# rf_bpf.net
KiCad netlist of a schematic drawn in Altium Designer
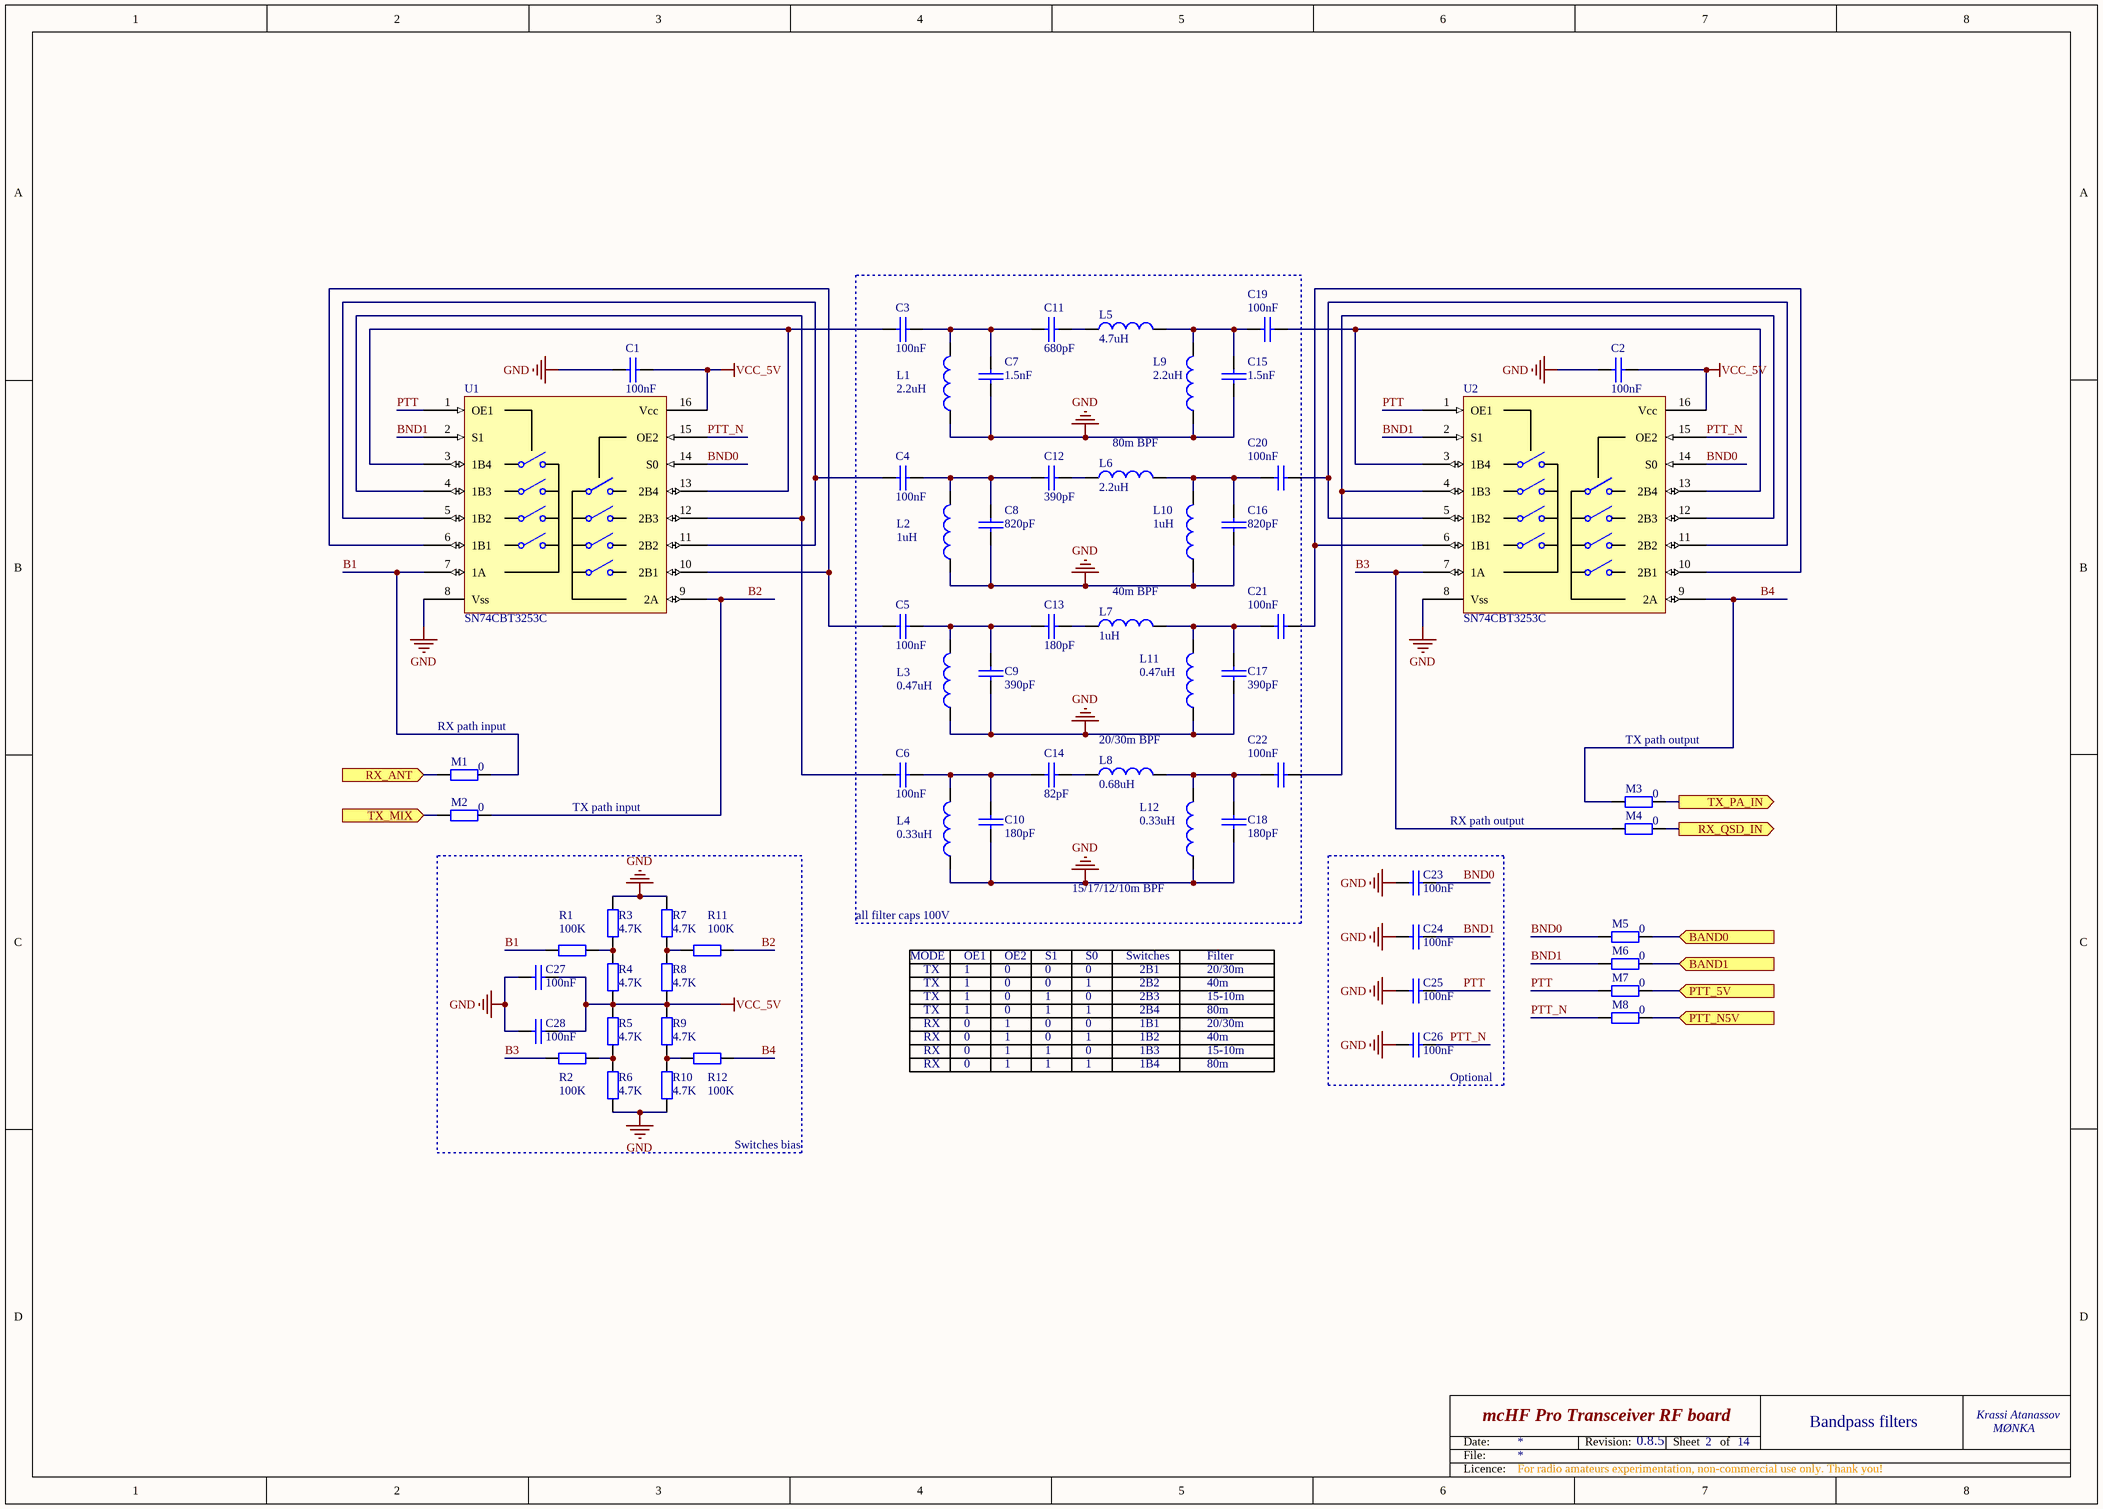
[diagram p0: rf_bpf.SchDoc]

(export (version "E")
  (design (tool "Eeschema 10.0.6"))
  (components
    (comp (ref "C1")
      (value "100nF")
      (footprint "0805")
      (description "Capacitor")
      (libsource (lib "mcHF_rf") (part "CAP"))
    )
    (comp (ref "C2")
      (value "100nF")
      (footprint "0805")
      (description "Capacitor")
      (libsource (lib "mcHF_rf") (part "CAP"))
    )
    (comp (ref "C3")
      (value "100nF")
      (footprint "0805")
      (description "Capacitor")
      (libsource (lib "mcHF_rf") (part "CAP"))
    )
    (comp (ref "C4")
      (value "100nF")
      (footprint "0805")
      (description "Capacitor")
      (libsource (lib "mcHF_rf") (part "CAP"))
    )
    (comp (ref "C5")
      (value "100nF")
      (footprint "0805")
      (description "Capacitor")
      (libsource (lib "mcHF_rf") (part "CAP"))
    )
    (comp (ref "C6")
      (value "100nF")
      (footprint "0805")
      (description "Capacitor")
      (libsource (lib "mcHF_rf") (part "CAP"))
    )
    (comp (ref "C7")
      (value "1.5nF")
      (footprint "0805")
      (description "Capacitor")
      (libsource (lib "mcHF_rf") (part "CAP"))
    )
    (comp (ref "C8")
      (value "820pF")
      (footprint "0805")
      (description "Capacitor")
      (libsource (lib "mcHF_rf") (part "CAP"))
    )
    (comp (ref "C9")
      (value "390pF")
      (footprint "0805")
      (description "Capacitor")
      (libsource (lib "mcHF_rf") (part "CAP"))
    )
    (comp (ref "C10")
      (value "180pF")
      (footprint "0805")
      (description "Capacitor")
      (libsource (lib "mcHF_rf") (part "CAP"))
    )
    (comp (ref "C11")
      (value "680pF")
      (footprint "0805")
      (description "Capacitor")
      (libsource (lib "mcHF_rf") (part "CAP"))
    )
    (comp (ref "C12")
      (value "390pF")
      (footprint "0805")
      (description "Capacitor")
      (libsource (lib "mcHF_rf") (part "CAP"))
    )
    (comp (ref "C13")
      (value "180pF")
      (footprint "0805")
      (description "Capacitor")
      (libsource (lib "mcHF_rf") (part "CAP"))
    )
    (comp (ref "C14")
      (value "82pF")
      (footprint "0805")
      (description "Capacitor")
      (libsource (lib "mcHF_rf") (part "CAP"))
    )
    (comp (ref "C15")
      (value "1.5nF")
      (footprint "0805")
      (description "Capacitor")
      (libsource (lib "mcHF_rf") (part "CAP"))
    )
    (comp (ref "C16")
      (value "820pF")
      (footprint "0805")
      (description "Capacitor")
      (libsource (lib "mcHF_rf") (part "CAP"))
    )
    (comp (ref "C17")
      (value "390pF")
      (footprint "0805")
      (description "Capacitor")
      (libsource (lib "mcHF_rf") (part "CAP"))
    )
    (comp (ref "C18")
      (value "180pF")
      (footprint "0805")
      (description "Capacitor")
      (libsource (lib "mcHF_rf") (part "CAP"))
    )
    (comp (ref "C19")
      (value "100nF")
      (footprint "0805")
      (description "Capacitor")
      (libsource (lib "mcHF_rf") (part "CAP"))
    )
    (comp (ref "C20")
      (value "100nF")
      (footprint "0805")
      (description "Capacitor")
      (libsource (lib "mcHF_rf") (part "CAP"))
    )
    (comp (ref "C21")
      (value "100nF")
      (footprint "0805")
      (description "Capacitor")
      (libsource (lib "mcHF_rf") (part "CAP"))
    )
    (comp (ref "C22")
      (value "100nF")
      (footprint "0805")
      (description "Capacitor")
      (libsource (lib "mcHF_rf") (part "CAP"))
    )
    (comp (ref "C23")
      (value "100nF")
      (footprint "0805")
      (description "Capacitor")
      (libsource (lib "mcHF_rf") (part "CAP"))
    )
    (comp (ref "C24")
      (value "100nF")
      (footprint "0805")
      (description "Capacitor")
      (libsource (lib "mcHF_rf") (part "CAP"))
    )
    (comp (ref "C25")
      (value "100nF")
      (footprint "0805")
      (description "Capacitor")
      (libsource (lib "mcHF_rf") (part "CAP"))
    )
    (comp (ref "C26")
      (value "100nF")
      (footprint "0805")
      (description "Capacitor")
      (libsource (lib "mcHF_rf") (part "CAP"))
    )
    (comp (ref "C27")
      (value "100nF")
      (footprint "0805")
      (description "Capacitor")
      (libsource (lib "mcHF_rf") (part "CAP"))
    )
    (comp (ref "C28")
      (value "100nF")
      (footprint "0805")
      (description "Capacitor")
      (libsource (lib "mcHF_rf") (part "CAP"))
    )
    (comp (ref "L1")
      (value "2.2uH")
      (footprint "0805")
      (description "INDUCTOR SMD")
      (libsource (lib "mcHF_rf") (part "BPF_IND"))
    )
    (comp (ref "L2")
      (value "1uH")
      (footprint "0805")
      (description "INDUCTOR SMD")
      (libsource (lib "mcHF_rf") (part "BPF_IND"))
    )
    (comp (ref "L3")
      (value "0.47uH")
      (footprint "0805")
      (description "INDUCTOR SMD")
      (libsource (lib "mcHF_rf") (part "BPF_IND"))
    )
    (comp (ref "L4")
      (value "0.33uH")
      (footprint "0805")
      (description "INDUCTOR SMD")
      (libsource (lib "mcHF_rf") (part "BPF_IND"))
    )
    (comp (ref "L5")
      (value "4.7uH")
      (footprint "0805")
      (description "INDUCTOR SMD")
      (libsource (lib "mcHF_rf") (part "BPF_IND"))
    )
    (comp (ref "L6")
      (value "2.2uH")
      (footprint "0805")
      (description "INDUCTOR SMD")
      (libsource (lib "mcHF_rf") (part "BPF_IND"))
    )
    (comp (ref "L7")
      (value "1uH")
      (footprint "0805")
      (description "INDUCTOR SMD")
      (libsource (lib "mcHF_rf") (part "BPF_IND"))
    )
    (comp (ref "L8")
      (value "0.68uH")
      (footprint "0805")
      (description "INDUCTOR SMD")
      (libsource (lib "mcHF_rf") (part "BPF_IND"))
    )
    (comp (ref "L9")
      (value "2.2uH")
      (footprint "0805")
      (description "INDUCTOR SMD")
      (libsource (lib "mcHF_rf") (part "BPF_IND"))
    )
    (comp (ref "L10")
      (value "1uH")
      (footprint "0805")
      (description "INDUCTOR SMD")
      (libsource (lib "mcHF_rf") (part "BPF_IND"))
    )
    (comp (ref "L11")
      (value "0.47uH")
      (footprint "0805")
      (description "INDUCTOR SMD")
      (libsource (lib "mcHF_rf") (part "BPF_IND"))
    )
    (comp (ref "L12")
      (value "0.33uH")
      (footprint "0805")
      (description "INDUCTOR SMD")
      (libsource (lib "mcHF_rf") (part "BPF_IND"))
    )
    (comp (ref "M1")
      (value "0")
      (footprint "0805")
      (description "Resistor")
      (libsource (lib "") (part "RES_2"))
    )
    (comp (ref "M2")
      (value "0")
      (footprint "0805")
      (description "Resistor")
      (libsource (lib "") (part "RES_2"))
    )
    (comp (ref "M3")
      (value "0")
      (footprint "0805")
      (description "Resistor")
      (libsource (lib "") (part "RES_2"))
    )
    (comp (ref "M4")
      (value "0")
      (footprint "0805")
      (description "Resistor")
      (libsource (lib "") (part "RES_2"))
    )
    (comp (ref "M5")
      (value "0")
      (footprint "0805")
      (description "Resistor")
      (libsource (lib "") (part "RES_2"))
    )
    (comp (ref "M6")
      (value "0")
      (footprint "0805")
      (description "Resistor")
      (libsource (lib "") (part "RES_2"))
    )
    (comp (ref "M7")
      (value "0")
      (footprint "0805")
      (description "Resistor")
      (libsource (lib "") (part "RES_2"))
    )
    (comp (ref "M8")
      (value "0")
      (footprint "0805")
      (description "Resistor")
      (libsource (lib "") (part "RES_2"))
    )
    (comp (ref "R1")
      (value "100K")
      (footprint "0805")
      (description "Resistor")
      (libsource (lib "mcHF_rf") (part "RES"))
    )
    (comp (ref "R2")
      (value "100K")
      (footprint "0805")
      (description "Resistor")
      (libsource (lib "mcHF_rf") (part "RES"))
    )
    (comp (ref "R3")
      (value "4.7K")
      (footprint "0805")
      (description "Resistor")
      (libsource (lib "") (part "RES_1"))
    )
    (comp (ref "R4")
      (value "4.7K")
      (footprint "0805")
      (description "Resistor")
      (libsource (lib "") (part "RES_1"))
    )
    (comp (ref "R5")
      (value "4.7K")
      (footprint "0805")
      (description "Resistor")
      (libsource (lib "") (part "RES_1"))
    )
    (comp (ref "R6")
      (value "4.7K")
      (footprint "0805")
      (description "Resistor")
      (libsource (lib "") (part "RES_1"))
    )
    (comp (ref "R7")
      (value "4.7K")
      (footprint "0805")
      (description "Resistor")
      (libsource (lib "") (part "RES_1"))
    )
    (comp (ref "R8")
      (value "4.7K")
      (footprint "0805")
      (description "Resistor")
      (libsource (lib "") (part "RES_1"))
    )
    (comp (ref "R9")
      (value "4.7K")
      (footprint "0805")
      (description "Resistor")
      (libsource (lib "") (part "RES_1"))
    )
    (comp (ref "R10")
      (value "4.7K")
      (footprint "0805")
      (description "Resistor")
      (libsource (lib "") (part "RES_1"))
    )
    (comp (ref "R11")
      (value "100K")
      (footprint "0805")
      (description "Resistor")
      (libsource (lib "mcHF_rf") (part "RES"))
    )
    (comp (ref "R12")
      (value "100K")
      (footprint "0805")
      (description "Resistor")
      (libsource (lib "mcHF_rf") (part "RES"))
    )
    (comp (ref "U1")
      (value "SN74CBT3253C")
      (footprint "SO-16")
      (description "Dual 4:1 Demux/Analog Switch")
      (libsource (lib "mcHF_rf") (part "SN74CBT3253C"))
    )
    (comp (ref "U2")
      (value "SN74CBT3253C")
      (footprint "SO-16")
      (description "Dual 4:1 Demux/Analog Switch")
      (libsource (lib "mcHF_rf") (part "SN74CBT3253C"))
    )
  )
  (nets
    (net (code "1") (name "/B1") (class "Default")
      (node (ref "M1") (pin "1") (pinfunction "1_1") (pintype "passive"))
      (node (ref "R1") (pin "1") (pinfunction "1_1") (pintype "passive"))
      (node (ref "U1") (pin "7") (pinfunction "1A_7") (pintype "bidirectional"))
    )
    (net (code "2") (name "/B2") (class "Default")
      (node (ref "M2") (pin "1") (pinfunction "1_1") (pintype "passive"))
      (node (ref "R11") (pin "2") (pinfunction "2_2") (pintype "passive"))
      (node (ref "U1") (pin "9") (pinfunction "2A_9") (pintype "bidirectional"))
    )
    (net (code "3") (name "/B3") (class "Default")
      (node (ref "M4") (pin "2") (pinfunction "2_2") (pintype "passive"))
      (node (ref "R2") (pin "1") (pinfunction "1_1") (pintype "passive"))
      (node (ref "U2") (pin "7") (pinfunction "1A_7") (pintype "bidirectional"))
    )
    (net (code "4") (name "/B4") (class "Default")
      (node (ref "M3") (pin "2") (pinfunction "2_2") (pintype "passive"))
      (node (ref "R12") (pin "2") (pinfunction "2_2") (pintype "passive"))
      (node (ref "U2") (pin "9") (pinfunction "2A_9") (pintype "bidirectional"))
    )
    (net (code "5") (name "/BAND0") (class "Default")
      (node (ref "M5") (pin "1") (pinfunction "1_1") (pintype "passive"))
    )
    (net (code "6") (name "/BAND1") (class "Default")
      (node (ref "M6") (pin "1") (pinfunction "1_1") (pintype "passive"))
    )
    (net (code "7") (name "/BND0") (class "Default")
      (node (ref "C23") (pin "1") (pinfunction "1_1") (pintype "passive"))
      (node (ref "M5") (pin "2") (pinfunction "2_2") (pintype "passive"))
      (node (ref "U1") (pin "14") (pinfunction "S0_14") (pintype "input"))
      (node (ref "U2") (pin "14") (pinfunction "S0_14") (pintype "input"))
    )
    (net (code "8") (name "/BND1") (class "Default")
      (node (ref "C24") (pin "1") (pinfunction "1_1") (pintype "passive"))
      (node (ref "M6") (pin "2") (pinfunction "2_2") (pintype "passive"))
      (node (ref "U1") (pin "2") (pinfunction "S1_2") (pintype "input"))
      (node (ref "U2") (pin "2") (pinfunction "S1_2") (pintype "input"))
    )
    (net (code "9") (name "/PTT") (class "Default")
      (node (ref "C25") (pin "1") (pinfunction "1_1") (pintype "passive"))
      (node (ref "M7") (pin "2") (pinfunction "2_2") (pintype "passive"))
      (node (ref "U1") (pin "1") (pinfunction "OE1_1") (pintype "input"))
      (node (ref "U2") (pin "1") (pinfunction "OE1_1") (pintype "input"))
    )
    (net (code "10") (name "/PTT_5V") (class "Default")
      (node (ref "M7") (pin "1") (pinfunction "1_1") (pintype "passive"))
    )
    (net (code "11") (name "/PTT_N") (class "Default")
      (node (ref "C26") (pin "1") (pinfunction "1_1") (pintype "passive"))
      (node (ref "M8") (pin "2") (pinfunction "2_2") (pintype "passive"))
      (node (ref "U1") (pin "15") (pinfunction "OE2_15") (pintype "input"))
      (node (ref "U2") (pin "15") (pinfunction "OE2_15") (pintype "input"))
    )
    (net (code "12") (name "/PTT_N5V") (class "Default")
      (node (ref "M8") (pin "1") (pinfunction "1_1") (pintype "passive"))
    )
    (net (code "13") (name "/RX_ANT") (class "Default")
      (node (ref "M1") (pin "2") (pinfunction "2_2") (pintype "passive"))
    )
    (net (code "14") (name "/RX_QSD_IN") (class "Default")
      (node (ref "M4") (pin "1") (pinfunction "1_1") (pintype "passive"))
    )
    (net (code "15") (name "/TX_MIX") (class "Default")
      (node (ref "M2") (pin "2") (pinfunction "2_2") (pintype "passive"))
    )
    (net (code "16") (name "/TX_PA_IN") (class "Default")
      (node (ref "M3") (pin "1") (pinfunction "1_1") (pintype "passive"))
    )
    (net (code "17") (name "GND") (class "Default")
      (node (ref "C1") (pin "2") (pinfunction "2_2") (pintype "passive"))
      (node (ref "C10") (pin "1") (pinfunction "1_1") (pintype "passive"))
      (node (ref "C15") (pin "2") (pinfunction "2_2") (pintype "passive"))
      (node (ref "C16") (pin "2") (pinfunction "2_2") (pintype "passive"))
      (node (ref "C17") (pin "1") (pinfunction "1_1") (pintype "passive"))
      (node (ref "C18") (pin "1") (pinfunction "1_1") (pintype "passive"))
      (node (ref "C2") (pin "2") (pinfunction "2_2") (pintype "passive"))
      (node (ref "C23") (pin "2") (pinfunction "2_2") (pintype "passive"))
      (node (ref "C24") (pin "2") (pinfunction "2_2") (pintype "passive"))
      (node (ref "C25") (pin "2") (pinfunction "2_2") (pintype "passive"))
      (node (ref "C26") (pin "2") (pinfunction "2_2") (pintype "passive"))
      (node (ref "C27") (pin "2") (pinfunction "2_2") (pintype "passive"))
      (node (ref "C28") (pin "2") (pinfunction "2_2") (pintype "passive"))
      (node (ref "C7") (pin "2") (pinfunction "2_2") (pintype "passive"))
      (node (ref "C8") (pin "2") (pinfunction "2_2") (pintype "passive"))
      (node (ref "C9") (pin "1") (pinfunction "1_1") (pintype "passive"))
      (node (ref "L1") (pin "1") (pinfunction "1_1") (pintype "passive"))
      (node (ref "L10") (pin "1") (pinfunction "1_1") (pintype "passive"))
      (node (ref "L11") (pin "1") (pinfunction "1_1") (pintype "passive"))
      (node (ref "L12") (pin "1") (pinfunction "1_1") (pintype "passive"))
      (node (ref "L2") (pin "1") (pinfunction "1_1") (pintype "passive"))
      (node (ref "L3") (pin "1") (pinfunction "1_1") (pintype "passive"))
      (node (ref "L4") (pin "1") (pinfunction "1_1") (pintype "passive"))
      (node (ref "L9") (pin "1") (pinfunction "1_1") (pintype "passive"))
      (node (ref "R10") (pin "2") (pinfunction "2_2") (pintype "passive"))
      (node (ref "R3") (pin "1") (pinfunction "1_1") (pintype "passive"))
      (node (ref "R6") (pin "2") (pinfunction "2_2") (pintype "passive"))
      (node (ref "R7") (pin "1") (pinfunction "1_1") (pintype "passive"))
      (node (ref "U1") (pin "8") (pinfunction "Vss_8") (pintype "power_in"))
      (node (ref "U2") (pin "8") (pinfunction "Vss_8") (pintype "power_in"))
    )
    (net (code "18") (name "Net-(C10-Pad2)") (class "Default")
      (node (ref "C10") (pin "2") (pinfunction "2_2") (pintype "passive"))
      (node (ref "C14") (pin "1") (pinfunction "1_1") (pintype "passive"))
      (node (ref "C6") (pin "1") (pinfunction "1_1") (pintype "passive"))
      (node (ref "L4") (pin "2") (pinfunction "2_2") (pintype "passive"))
    )
    (net (code "19") (name "Net-(C11-Pad1)") (class "Default")
      (node (ref "C11") (pin "1") (pinfunction "1_1") (pintype "passive"))
      (node (ref "C3") (pin "1") (pinfunction "1_1") (pintype "passive"))
      (node (ref "C7") (pin "1") (pinfunction "1_1") (pintype "passive"))
      (node (ref "L1") (pin "2") (pinfunction "2_2") (pintype "passive"))
    )
    (net (code "20") (name "Net-(C11-Pad2)") (class "Default")
      (node (ref "C11") (pin "2") (pinfunction "2_2") (pintype "passive"))
      (node (ref "L5") (pin "1") (pinfunction "1_1") (pintype "passive"))
    )
    (net (code "21") (name "Net-(C12-Pad1)") (class "Default")
      (node (ref "C12") (pin "1") (pinfunction "1_1") (pintype "passive"))
      (node (ref "C4") (pin "1") (pinfunction "1_1") (pintype "passive"))
      (node (ref "C8") (pin "1") (pinfunction "1_1") (pintype "passive"))
      (node (ref "L2") (pin "2") (pinfunction "2_2") (pintype "passive"))
    )
    (net (code "22") (name "Net-(C12-Pad2)") (class "Default")
      (node (ref "C12") (pin "2") (pinfunction "2_2") (pintype "passive"))
      (node (ref "L6") (pin "1") (pinfunction "1_1") (pintype "passive"))
    )
    (net (code "23") (name "Net-(C13-Pad1)") (class "Default")
      (node (ref "C13") (pin "1") (pinfunction "1_1") (pintype "passive"))
      (node (ref "C5") (pin "1") (pinfunction "1_1") (pintype "passive"))
      (node (ref "C9") (pin "2") (pinfunction "2_2") (pintype "passive"))
      (node (ref "L3") (pin "2") (pinfunction "2_2") (pintype "passive"))
    )
    (net (code "24") (name "Net-(C13-Pad2)") (class "Default")
      (node (ref "C13") (pin "2") (pinfunction "2_2") (pintype "passive"))
      (node (ref "L7") (pin "1") (pinfunction "1_1") (pintype "passive"))
    )
    (net (code "25") (name "Net-(C14-Pad2)") (class "Default")
      (node (ref "C14") (pin "2") (pinfunction "2_2") (pintype "passive"))
      (node (ref "L8") (pin "1") (pinfunction "1_1") (pintype "passive"))
    )
    (net (code "26") (name "Net-(C15-Pad1)") (class "Default")
      (node (ref "C15") (pin "1") (pinfunction "1_1") (pintype "passive"))
      (node (ref "C19") (pin "2") (pinfunction "2_2") (pintype "passive"))
      (node (ref "L5") (pin "2") (pinfunction "2_2") (pintype "passive"))
      (node (ref "L9") (pin "2") (pinfunction "2_2") (pintype "passive"))
    )
    (net (code "27") (name "Net-(C16-Pad1)") (class "Default")
      (node (ref "C16") (pin "1") (pinfunction "1_1") (pintype "passive"))
      (node (ref "C20") (pin "2") (pinfunction "2_2") (pintype "passive"))
      (node (ref "L10") (pin "2") (pinfunction "2_2") (pintype "passive"))
      (node (ref "L6") (pin "2") (pinfunction "2_2") (pintype "passive"))
    )
    (net (code "28") (name "Net-(C17-Pad2)") (class "Default")
      (node (ref "C17") (pin "2") (pinfunction "2_2") (pintype "passive"))
      (node (ref "C21") (pin "2") (pinfunction "2_2") (pintype "passive"))
      (node (ref "L11") (pin "2") (pinfunction "2_2") (pintype "passive"))
      (node (ref "L7") (pin "2") (pinfunction "2_2") (pintype "passive"))
    )
    (net (code "29") (name "Net-(C18-Pad2)") (class "Default")
      (node (ref "C18") (pin "2") (pinfunction "2_2") (pintype "passive"))
      (node (ref "C22") (pin "2") (pinfunction "2_2") (pintype "passive"))
      (node (ref "L12") (pin "2") (pinfunction "2_2") (pintype "passive"))
      (node (ref "L8") (pin "2") (pinfunction "2_2") (pintype "passive"))
    )
    (net (code "30") (name "Net-(R1-Pad2)") (class "Default")
      (node (ref "R1") (pin "2") (pinfunction "2_2") (pintype "passive"))
      (node (ref "R3") (pin "2") (pinfunction "2_2") (pintype "passive"))
      (node (ref "R4") (pin "1") (pinfunction "1_1") (pintype "passive"))
    )
    (net (code "31") (name "Net-(R2-Pad2)") (class "Default")
      (node (ref "R2") (pin "2") (pinfunction "2_2") (pintype "passive"))
      (node (ref "R5") (pin "2") (pinfunction "2_2") (pintype "passive"))
      (node (ref "R6") (pin "1") (pinfunction "1_1") (pintype "passive"))
    )
    (net (code "32") (name "Net-(R10-Pad1)") (class "Default")
      (node (ref "R10") (pin "1") (pinfunction "1_1") (pintype "passive"))
      (node (ref "R12") (pin "1") (pinfunction "1_1") (pintype "passive"))
      (node (ref "R9") (pin "2") (pinfunction "2_2") (pintype "passive"))
    )
    (net (code "33") (name "Net-(R11-Pad1)") (class "Default")
      (node (ref "R11") (pin "1") (pinfunction "1_1") (pintype "passive"))
      (node (ref "R7") (pin "2") (pinfunction "2_2") (pintype "passive"))
      (node (ref "R8") (pin "1") (pinfunction "1_1") (pintype "passive"))
    )
    (net (code "34") (name "Net-(U1-1B1)") (class "Default")
      (node (ref "C5") (pin "2") (pinfunction "2_2") (pintype "passive"))
      (node (ref "U1") (pin "10") (pinfunction "2B1_10") (pintype "bidirectional"))
      (node (ref "U1") (pin "6") (pinfunction "1B1_6") (pintype "bidirectional"))
    )
    (net (code "35") (name "Net-(U1-1B2)") (class "Default")
      (node (ref "C4") (pin "2") (pinfunction "2_2") (pintype "passive"))
      (node (ref "U1") (pin "11") (pinfunction "2B2_11") (pintype "bidirectional"))
      (node (ref "U1") (pin "5") (pinfunction "1B2_5") (pintype "bidirectional"))
    )
    (net (code "36") (name "Net-(U1-1B3)") (class "Default")
      (node (ref "C6") (pin "2") (pinfunction "2_2") (pintype "passive"))
      (node (ref "U1") (pin "12") (pinfunction "2B3_12") (pintype "bidirectional"))
      (node (ref "U1") (pin "4") (pinfunction "1B3_4") (pintype "bidirectional"))
    )
    (net (code "37") (name "Net-(U1-1B4)") (class "Default")
      (node (ref "C3") (pin "2") (pinfunction "2_2") (pintype "passive"))
      (node (ref "U1") (pin "13") (pinfunction "2B4_13") (pintype "bidirectional"))
      (node (ref "U1") (pin "3") (pinfunction "1B4_3") (pintype "bidirectional"))
    )
    (net (code "38") (name "Net-(U2-1B1)") (class "Default")
      (node (ref "C21") (pin "1") (pinfunction "1_1") (pintype "passive"))
      (node (ref "U2") (pin "10") (pinfunction "2B1_10") (pintype "bidirectional"))
      (node (ref "U2") (pin "6") (pinfunction "1B1_6") (pintype "bidirectional"))
    )
    (net (code "39") (name "Net-(U2-1B2)") (class "Default")
      (node (ref "C20") (pin "1") (pinfunction "1_1") (pintype "passive"))
      (node (ref "U2") (pin "11") (pinfunction "2B2_11") (pintype "bidirectional"))
      (node (ref "U2") (pin "5") (pinfunction "1B2_5") (pintype "bidirectional"))
    )
    (net (code "40") (name "Net-(U2-1B3)") (class "Default")
      (node (ref "C22") (pin "1") (pinfunction "1_1") (pintype "passive"))
      (node (ref "U2") (pin "12") (pinfunction "2B3_12") (pintype "bidirectional"))
      (node (ref "U2") (pin "4") (pinfunction "1B3_4") (pintype "bidirectional"))
    )
    (net (code "41") (name "Net-(U2-1B4)") (class "Default")
      (node (ref "C19") (pin "1") (pinfunction "1_1") (pintype "passive"))
      (node (ref "U2") (pin "13") (pinfunction "2B4_13") (pintype "bidirectional"))
      (node (ref "U2") (pin "3") (pinfunction "1B4_3") (pintype "bidirectional"))
    )
    (net (code "42") (name "VCC_5V") (class "Default")
      (node (ref "C1") (pin "1") (pinfunction "1_1") (pintype "passive"))
      (node (ref "C2") (pin "1") (pinfunction "1_1") (pintype "passive"))
      (node (ref "C27") (pin "1") (pinfunction "1_1") (pintype "passive"))
      (node (ref "C28") (pin "1") (pinfunction "1_1") (pintype "passive"))
      (node (ref "R4") (pin "2") (pinfunction "2_2") (pintype "passive"))
      (node (ref "R5") (pin "1") (pinfunction "1_1") (pintype "passive"))
      (node (ref "R8") (pin "2") (pinfunction "2_2") (pintype "passive"))
      (node (ref "R9") (pin "1") (pinfunction "1_1") (pintype "passive"))
      (node (ref "U1") (pin "16") (pinfunction "Vcc_16") (pintype "power_in"))
      (node (ref "U2") (pin "16") (pinfunction "Vcc_16") (pintype "power_in"))
    )
  )
)
